# bluenrg.net
KiCad netlist of a schematic drawn in Altium Designer
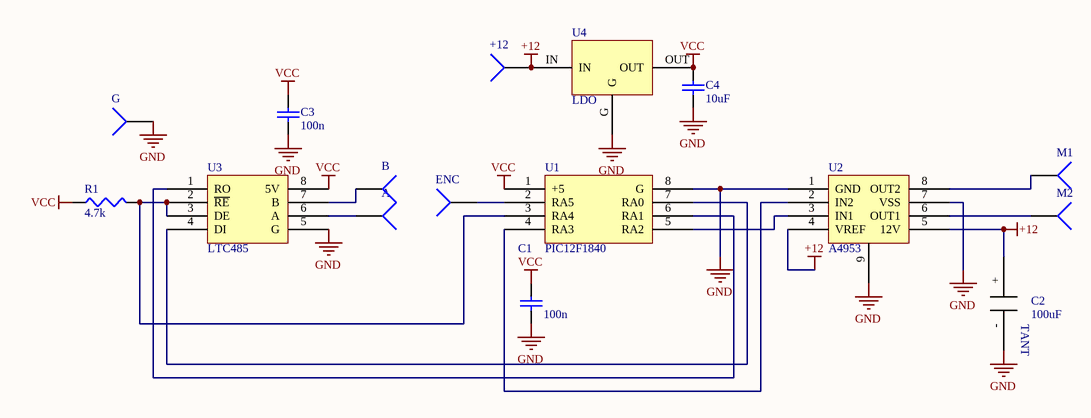
[diagram p0: bluenrg.SchDoc]

(export (version "E")
  (design (tool "Eeschema 10.0.6"))
  (components
    (comp (ref "+12")
      (value "+12")
      (footprint "MY_PAD")
      (description "Socket")
      (fields (field (name "PUBLISHER") "Altium Limited"))
      (libsource (lib "Miscellaneous Connectors") (part "Socket"))
    )
    (comp (ref "A")
      (value "A")
      (footprint "MY_PAD")
      (description "Socket")
      (fields (field (name "PUBLISHER") "Altium Limited"))
      (libsource (lib "Miscellaneous Connectors") (part "Socket"))
    )
    (comp (ref "B")
      (value "B")
      (footprint "MY_PAD")
      (description "Socket")
      (fields (field (name "PUBLISHER") "Altium Limited"))
      (libsource (lib "Miscellaneous Connectors") (part "Socket"))
    )
    (comp (ref "C1")
      (value "100n")
      (footprint "MY_0603")
      (description "Capacitor (Semiconductor SIM Model)")
      (fields (field (name "PUBLISHER") "Altium Limited"))
      (libsource (lib "Miscellaneous Devices") (part "Cap Semi"))
    )
    (comp (ref "C2") (value "100uF") (footprint "100uf_tant") (libsource (lib "components") (part "C_TANT")))
    (comp (ref "C3")
      (value "100n")
      (footprint "MY_0603")
      (description "Capacitor (Semiconductor SIM Model)")
      (fields (field (name "PUBLISHER") "Altium Limited"))
      (libsource (lib "Miscellaneous Devices") (part "Cap Semi"))
    )
    (comp (ref "C4")
      (value "10uF")
      (footprint "MY_0805")
      (description "Capacitor (Semiconductor SIM Model)")
      (fields (field (name "PUBLISHER") "Altium Limited"))
      (libsource (lib "Miscellaneous Devices") (part "Cap Semi"))
    )
    (comp (ref "ENC")
      (value "A")
      (footprint "MY_PAD")
      (description "Socket")
      (fields (field (name "PUBLISHER") "Altium Limited"))
      (libsource (lib "Miscellaneous Connectors") (part "Socket"))
    )
    (comp (ref "G")
      (value "G")
      (footprint "MY_PAD")
      (description "Socket")
      (fields (field (name "PUBLISHER") "Altium Limited"))
      (libsource (lib "Miscellaneous Connectors") (part "Socket"))
    )
    (comp (ref "M1")
      (value "M1")
      (footprint "MOTOR_18mm")
      (description "Socket")
      (fields (field (name "PUBLISHER") "Altium Limited"))
      (libsource (lib "Miscellaneous Connectors") (part "Socket"))
    )
    (comp (ref "M2")
      (value "M2")
      (footprint "MOTOR_18mm")
      (description "Socket")
      (fields (field (name "PUBLISHER") "Altium Limited"))
      (libsource (lib "Miscellaneous Connectors") (part "Socket"))
    )
    (comp (ref "R1")
      (value "4.7k")
      (footprint "MY_0603")
      (description "Resistor")
      (fields (field (name "PUBLISHER") "Altium Limited"))
      (libsource (lib "Miscellaneous Devices") (part "Res3"))
    )
    (comp (ref "U1")
      (value "PIC12F1840")
      (footprint "MY_SOIC8N")
      (libsource (lib "components") (part "PIC12F1840"))
    )
    (comp (ref "U2") (value "A4953") (footprint "MY_SOIC8N_TP") (libsource (lib "components") (part "A4953")))
    (comp (ref "U3") (value "LTC485") (footprint "MY_SOIC8N") (libsource (lib "components") (part "LTC485")))
    (comp (ref "U4") (value "LDO") (footprint "L78L") (libsource (lib "components") (part "LDO")))
  )
  (nets
    (net (code "1") (name "+12") (class "Default")
      (node (ref "+12") (pin "1") (pinfunction "1_1") (pintype "passive"))
      (node (ref "C2") (pin "+") (pinfunction "+_+") (pintype "passive"))
      (node (ref "U2") (pin "4") (pinfunction "VREF_4") (pintype "passive"))
      (node (ref "U2") (pin "5") (pinfunction "12V_5") (pintype "passive"))
      (node (ref "U4") (pin "IN") (pinfunction "IN_IN") (pintype "passive"))
    )
    (net (code "2") (name "GND") (class "Default")
      (node (ref "C1") (pin "1") (pinfunction "1_1") (pintype "passive"))
      (node (ref "C2") (pin "-") (pinfunction "-_-") (pintype "passive"))
      (node (ref "C3") (pin "1") (pinfunction "1_1") (pintype "passive"))
      (node (ref "C4") (pin "1") (pinfunction "1_1") (pintype "passive"))
      (node (ref "G") (pin "1") (pinfunction "1_1") (pintype "passive"))
      (node (ref "U1") (pin "8") (pinfunction "G_8") (pintype "passive"))
      (node (ref "U2") (pin "1") (pinfunction "GND_1") (pintype "passive"))
      (node (ref "U2") (pin "7") (pinfunction "VSS_7") (pintype "passive"))
      (node (ref "U2") (pin "9") (pintype "passive"))
      (node (ref "U3") (pin "5") (pinfunction "G_5") (pintype "passive"))
      (node (ref "U4") (pin "G") (pinfunction "G_G") (pintype "passive"))
    )
    (net (code "3") (name "Net-(U1-RA0)") (class "Default")
      (node (ref "U1") (pin "7") (pinfunction "RA0_7") (pintype "passive"))
      (node (ref "U3") (pin "4") (pinfunction "DI_4") (pintype "passive"))
    )
    (net (code "4") (name "Net-(U1-RA1)") (class "Default")
      (node (ref "U1") (pin "6") (pinfunction "RA1_6") (pintype "passive"))
      (node (ref "U3") (pin "1") (pinfunction "RO_1") (pintype "passive"))
    )
    (net (code "5") (name "Net-(U1-RA2)") (class "Default")
      (node (ref "U1") (pin "5") (pinfunction "RA2_5") (pintype "passive"))
      (node (ref "U2") (pin "3") (pinfunction "IN1_3") (pintype "passive"))
    )
    (net (code "6") (name "Net-(U1-RA3)") (class "Default")
      (node (ref "U1") (pin "4") (pinfunction "RA3_4") (pintype "passive"))
      (node (ref "U2") (pin "2") (pinfunction "IN2_2") (pintype "passive"))
    )
    (net (code "7") (name "Net-(U1-RA4)") (class "Default")
      (node (ref "R1") (pin "2") (pinfunction "2_2") (pintype "passive"))
      (node (ref "U1") (pin "3") (pinfunction "RA4_3") (pintype "passive"))
      (node (ref "U3") (pin "2") (pinfunction "~{RE}_2") (pintype "passive"))
      (node (ref "U3") (pin "3") (pinfunction "DE_3") (pintype "passive"))
    )
    (net (code "8") (name "Net-(U1-RA5)") (class "Default")
      (node (ref "ENC") (pin "1") (pinfunction "1_1") (pintype "passive"))
      (node (ref "U1") (pin "2") (pinfunction "RA5_2") (pintype "passive"))
    )
    (net (code "9") (name "Net-(U2-OUT1)") (class "Default")
      (node (ref "M2") (pin "1") (pinfunction "1_1") (pintype "passive"))
      (node (ref "U2") (pin "6") (pinfunction "OUT1_6") (pintype "passive"))
    )
    (net (code "10") (name "Net-(U2-OUT2)") (class "Default")
      (node (ref "M1") (pin "1") (pinfunction "1_1") (pintype "passive"))
      (node (ref "U2") (pin "8") (pinfunction "OUT2_8") (pintype "passive"))
    )
    (net (code "11") (name "Net-(U3-A)") (class "Default")
      (node (ref "A") (pin "1") (pinfunction "1_1") (pintype "passive"))
      (node (ref "U3") (pin "6") (pinfunction "A_6") (pintype "passive"))
    )
    (net (code "12") (name "Net-(U3-B)") (class "Default")
      (node (ref "B") (pin "1") (pinfunction "1_1") (pintype "passive"))
      (node (ref "U3") (pin "7") (pinfunction "B_7") (pintype "passive"))
    )
    (net (code "13") (name "VCC") (class "Default")
      (node (ref "C1") (pin "2") (pinfunction "2_2") (pintype "passive"))
      (node (ref "C3") (pin "2") (pinfunction "2_2") (pintype "passive"))
      (node (ref "C4") (pin "2") (pinfunction "2_2") (pintype "passive"))
      (node (ref "R1") (pin "1") (pinfunction "1_1") (pintype "passive"))
      (node (ref "U1") (pin "1") (pinfunction "+5_1") (pintype "passive"))
      (node (ref "U3") (pin "8") (pinfunction "5V_8") (pintype "passive"))
      (node (ref "U4") (pin "OUT") (pinfunction "OUT_OUT") (pintype "passive"))
    )
  )
)
